# power-io.net
KiCad netlist of a schematic drawn in Altium Designer
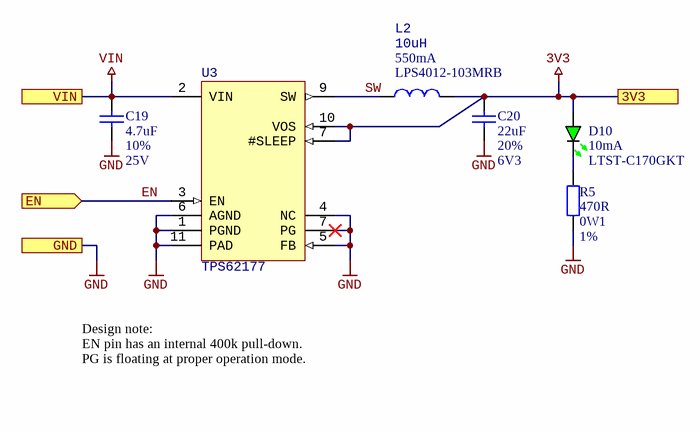
[diagram p0: power-io.SchDoc]

(export (version "E")
  (design (tool "Eeschema 10.0.6"))
  (components
    (comp (ref "C19")
      (value "4.7uF")
      (footprint "CAPC2012N")
      (description "Capacitor")
      (fields (field (name "TOLERANCE") "10%") (field (name "VOLTAGE") "25V"))
      (libsource (lib "passives") (part "Capacitor"))
    )
    (comp (ref "C20")
      (value "22uF")
      (footprint "CAPC2012N")
      (description "Capacitor")
      (fields (field (name "TOLERANCE") "20%") (field (name "VOLTAGE") "6V3"))
      (libsource (lib "passives") (part "Capacitor"))
    )
    (comp (ref "D10")
      (value "Led Green")
      (footprint "CD2012-0805-GRN")
      (description "Typical GRN LED")
      (fields (field (name "CURRENT") "10mA") (field (name "MANID") "LTST-C170GKT"))
      (libsource (lib "semicon") (part "Led Green"))
    )
    (comp (ref "L2")
      (value "10uH")
      (footprint "LPS4012")
      (fields (field (name "CURRENT") "550mA") (field (name "MANID") "LPS4012-103MRB"))
      (libsource (lib "passives") (part "Inductor"))
    )
    (comp (ref "R5")
      (value "470R")
      (footprint "RESC1608N")
      (description "Resistor")
      (fields (field (name "POWER") "0W1") (field (name "TOLERANCE") "1%"))
      (libsource (lib "passives") (part "Resistor"))
    )
    (comp (ref "U3")
      (value "TPS62177")
      (footprint "WSON10")
      (description "TPS6217x 28-V, 0.5-A Step-Down Converter With Sleep Mode")
      (libsource (lib "power") (part "TPS6217x"))
    )
  )
  (nets
    (net (code "1") (name "/EN") (class "Default")
      (node (ref "U3") (pin "3") (pinfunction "EN_3") (pintype "input"))
    )
    (net (code "2") (name "/SW") (class "Default")
      (node (ref "L2") (pin "2") (pinfunction "2_2") (pintype "passive"))
      (node (ref "U3") (pin "9") (pinfunction "SW_9") (pintype "output"))
    )
    (net (code "3") (name "3V3") (class "Default")
      (node (ref "C20") (pin "2") (pinfunction "2_2") (pintype "passive"))
      (node (ref "D10") (pin "1") (pinfunction "A_1") (pintype "passive"))
      (node (ref "L2") (pin "1") (pinfunction "1_1") (pintype "passive"))
      (node (ref "U3") (pin "10") (pinfunction "VOS_10") (pintype "input"))
      (node (ref "U3") (pin "7") (pinfunction "#SLEEP_7") (pintype "input"))
    )
    (net (code "4") (name "GND") (class "Default")
      (node (ref "C19") (pin "1") (pinfunction "1_1") (pintype "passive"))
      (node (ref "C20") (pin "1") (pinfunction "1_1") (pintype "passive"))
      (node (ref "R5") (pin "1") (pinfunction "1_1") (pintype "passive"))
      (node (ref "U3") (pin "1") (pinfunction "PGND_1") (pintype "power_in"))
      (node (ref "U3") (pin "11") (pinfunction "PAD_11") (pintype "power_in"))
      (node (ref "U3") (pin "4") (pinfunction "NC_4") (pintype "passive"))
      (node (ref "U3") (pin "5") (pinfunction "FB_5") (pintype "input"))
      (node (ref "U3") (pin "6") (pinfunction "AGND_6") (pintype "power_in"))
      (node (ref "U3") (pin "7") (pinfunction "PG_7") (pintype "open_collector"))
    )
    (net (code "5") (name "Net-(D10-K)") (class "Default")
      (node (ref "D10") (pin "2") (pinfunction "K_2") (pintype "passive"))
      (node (ref "R5") (pin "2") (pinfunction "2_2") (pintype "passive"))
    )
    (net (code "6") (name "VIN") (class "Default")
      (node (ref "C19") (pin "2") (pinfunction "2_2") (pintype "passive"))
      (node (ref "U3") (pin "2") (pinfunction "VIN_2") (pintype "power_in"))
    )
  )
)
